# Sheet1.net
KiCad netlist of a schematic drawn in Altium Designer
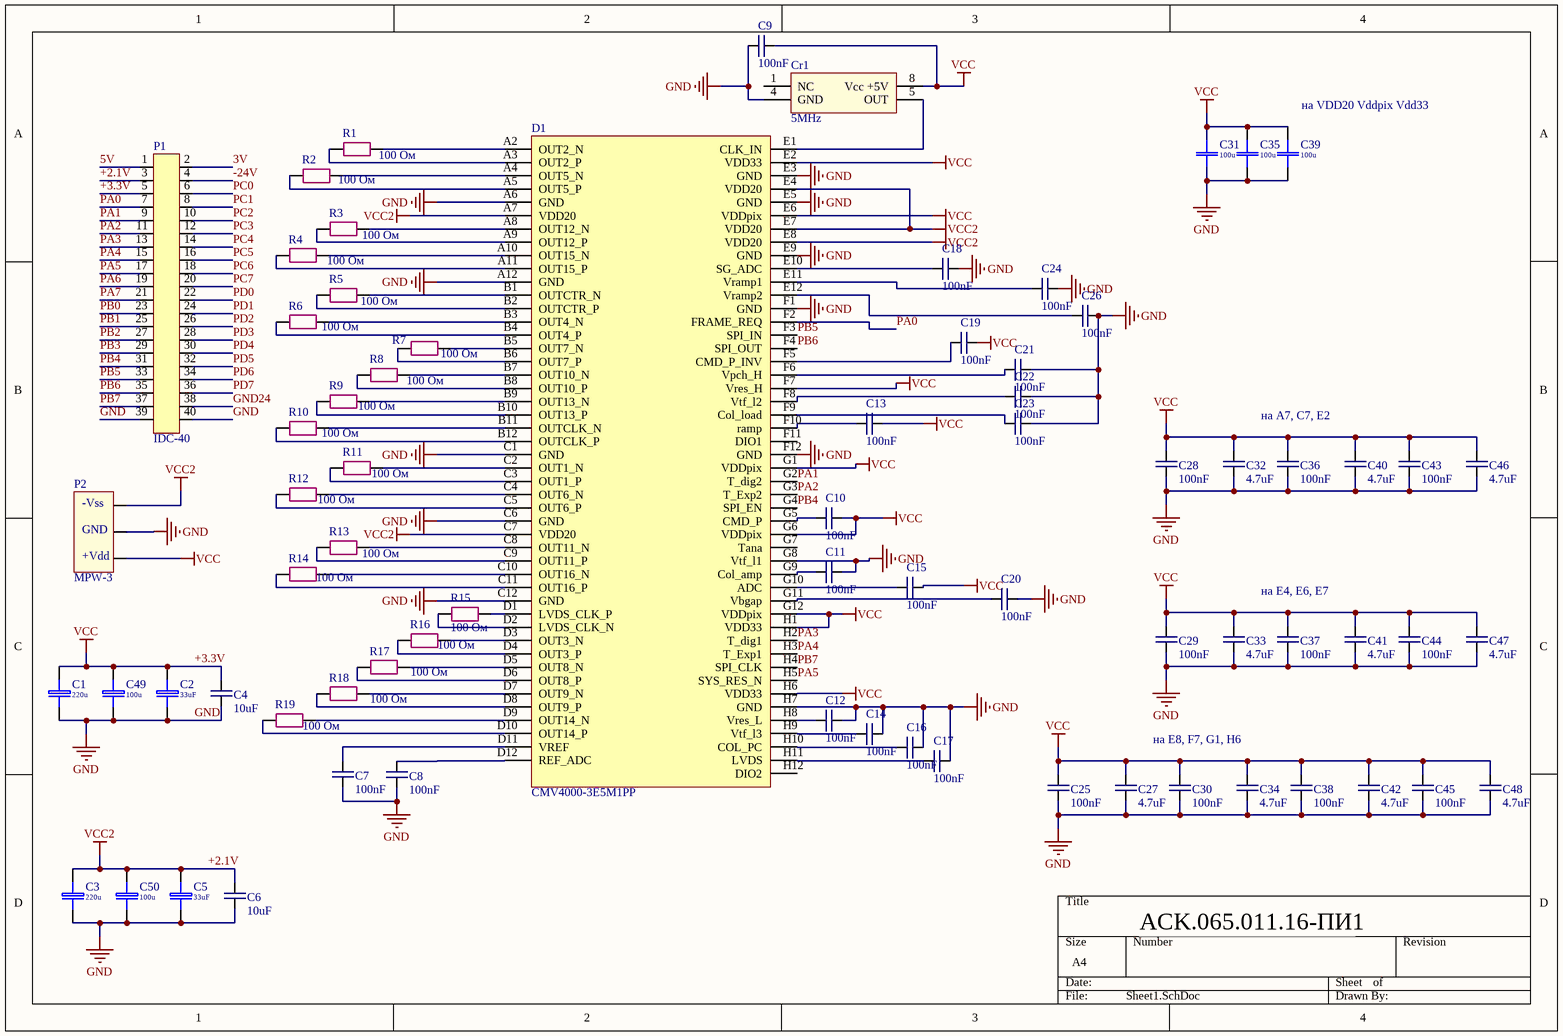
[diagram p0: Sheet1.SchDoc]

(export (version "E")
  (design (tool "Eeschema 10.0.6"))
  (components
    (comp (ref "C1")
      (value "220u")
      (footprint "EL SMD Case D D6.3x6.6 h7.7(0605)")
      (description "EL 25V SMD Case C D6.3x6.6 h7.7")
      (libsource (lib "SMD-RCL") (part "EL 100u/25V"))
    )
    (comp (ref "C2")
      (value "33uF")
      (footprint "EL Case B (3528-21)")
      (description "EL Tantalum Case B (3528-21)")
      (libsource (lib "SMD-RCL") (part "EL Case B (3528-21)"))
    )
    (comp (ref "C3")
      (value "220u")
      (footprint "EL SMD Case D D6.3x6.6 h7.7(0605)")
      (description "EL 25V SMD Case C D6.3x6.6 h7.7")
      (libsource (lib "SMD-RCL") (part "EL 100u/25V"))
    )
    (comp (ref "C4") (value "10uF") (footprint "RCU:C_0805") (libsource (lib "RCU") (part "capacitor 0805")))
    (comp (ref "C5")
      (value "33uF")
      (footprint "EL Case B (3528-21)")
      (description "EL Tantalum Case B (3528-21)")
      (libsource (lib "SMD-RCL") (part "EL Case B (3528-21)"))
    )
    (comp (ref "C6") (value "10uF") (footprint "RCU:C_0805") (libsource (lib "RCU") (part "capacitor 0805")))
    (comp (ref "C7") (value "100nF") (footprint "RCU:C_0805") (libsource (lib "RCU") (part "capacitor 0805")))
    (comp (ref "C8") (value "100nF") (footprint "RCU:C_0805") (libsource (lib "RCU") (part "capacitor 0805")))
    (comp (ref "C9") (value "100nF") (footprint "RCU:C_0805") (libsource (lib "RCU") (part "capacitor 0805")))
    (comp (ref "C10")
      (value "100nF")
      (footprint "RCU:C_0805")
      (libsource (lib "RCU") (part "capacitor 0805"))
    )
    (comp (ref "C11")
      (value "100nF")
      (footprint "RCU:C_0805")
      (libsource (lib "RCU") (part "capacitor 0805"))
    )
    (comp (ref "C12")
      (value "100nF")
      (footprint "RCU:C_0805")
      (libsource (lib "RCU") (part "capacitor 0805"))
    )
    (comp (ref "C13")
      (value "100nF")
      (footprint "RCU:C_0805")
      (libsource (lib "RCU") (part "capacitor 0805"))
    )
    (comp (ref "C14")
      (value "100nF")
      (footprint "RCU:C_0805")
      (libsource (lib "RCU") (part "capacitor 0805"))
    )
    (comp (ref "C15")
      (value "100nF")
      (footprint "RCU:C_0805")
      (libsource (lib "RCU") (part "capacitor 0805"))
    )
    (comp (ref "C16")
      (value "100nF")
      (footprint "RCU:C_0805")
      (libsource (lib "RCU") (part "capacitor 0805"))
    )
    (comp (ref "C17")
      (value "100nF")
      (footprint "RCU:C_0805")
      (libsource (lib "RCU") (part "capacitor 0805"))
    )
    (comp (ref "C18")
      (value "100nF")
      (footprint "RCU:C_0805")
      (libsource (lib "RCU") (part "capacitor 0805"))
    )
    (comp (ref "C19")
      (value "100nF")
      (footprint "RCU:C_0805")
      (libsource (lib "RCU") (part "capacitor 0805"))
    )
    (comp (ref "C20")
      (value "100nF")
      (footprint "RCU:C_0805")
      (libsource (lib "RCU") (part "capacitor 0805"))
    )
    (comp (ref "C21")
      (value "100nF")
      (footprint "RCU:C_0805")
      (libsource (lib "RCU") (part "capacitor 0805"))
    )
    (comp (ref "C22")
      (value "100nF")
      (footprint "RCU:C_0805")
      (libsource (lib "RCU") (part "capacitor 0805"))
    )
    (comp (ref "C23")
      (value "100nF")
      (footprint "RCU:C_0805")
      (libsource (lib "RCU") (part "capacitor 0805"))
    )
    (comp (ref "C24")
      (value "100nF")
      (footprint "RCU:C_0805")
      (libsource (lib "RCU") (part "capacitor 0805"))
    )
    (comp (ref "C25")
      (value "100nF")
      (footprint "RCU:C_0805")
      (libsource (lib "RCU") (part "capacitor 0805"))
    )
    (comp (ref "C26")
      (value "100nF")
      (footprint "RCU:C_0805")
      (libsource (lib "RCU") (part "capacitor 0805"))
    )
    (comp (ref "C27")
      (value "4.7uF")
      (footprint "RCU:C_0805")
      (libsource (lib "RCU") (part "capacitor 0805"))
    )
    (comp (ref "C28")
      (value "100nF")
      (footprint "RCU:C_0805")
      (libsource (lib "RCU") (part "capacitor 0805"))
    )
    (comp (ref "C29")
      (value "100nF")
      (footprint "RCU:C_0805")
      (libsource (lib "RCU") (part "capacitor 0805"))
    )
    (comp (ref "C30")
      (value "100nF")
      (footprint "RCU:C_0805")
      (libsource (lib "RCU") (part "capacitor 0805"))
    )
    (comp (ref "C31")
      (value "100u")
      (footprint "C1206(3216)")
      (description "SMD-1206 1000V X7R 10%")
      (libsource (lib "SMD-RCL") (part "C-1206  1000V 1n"))
    )
    (comp (ref "C32")
      (value "4.7uF")
      (footprint "RCU:C_0805")
      (libsource (lib "RCU") (part "capacitor 0805"))
    )
    (comp (ref "C33")
      (value "4.7uF")
      (footprint "RCU:C_0805")
      (libsource (lib "RCU") (part "capacitor 0805"))
    )
    (comp (ref "C34")
      (value "4.7uF")
      (footprint "RCU:C_0805")
      (libsource (lib "RCU") (part "capacitor 0805"))
    )
    (comp (ref "C35")
      (value "100u")
      (footprint "C1206(3216)")
      (description "SMD-1206 1000V X7R 10%")
      (libsource (lib "SMD-RCL") (part "C-1206  1000V 1n"))
    )
    (comp (ref "C36")
      (value "100nF")
      (footprint "RCU:C_0805")
      (libsource (lib "RCU") (part "capacitor 0805"))
    )
    (comp (ref "C37")
      (value "100nF")
      (footprint "RCU:C_0805")
      (libsource (lib "RCU") (part "capacitor 0805"))
    )
    (comp (ref "C38")
      (value "100nF")
      (footprint "RCU:C_0805")
      (libsource (lib "RCU") (part "capacitor 0805"))
    )
    (comp (ref "C39")
      (value "100u")
      (footprint "C1206(3216)")
      (description "SMD-1206 1000V X7R 10%")
      (libsource (lib "SMD-RCL") (part "C-1206  1000V 1n"))
    )
    (comp (ref "C40")
      (value "4.7uF")
      (footprint "RCU:C_0805")
      (libsource (lib "RCU") (part "capacitor 0805"))
    )
    (comp (ref "C41")
      (value "4.7uF")
      (footprint "RCU:C_0805")
      (libsource (lib "RCU") (part "capacitor 0805"))
    )
    (comp (ref "C42")
      (value "4.7uF")
      (footprint "RCU:C_0805")
      (libsource (lib "RCU") (part "capacitor 0805"))
    )
    (comp (ref "C43")
      (value "100nF")
      (footprint "RCU:C_0805")
      (libsource (lib "RCU") (part "capacitor 0805"))
    )
    (comp (ref "C44")
      (value "100nF")
      (footprint "RCU:C_0805")
      (libsource (lib "RCU") (part "capacitor 0805"))
    )
    (comp (ref "C45")
      (value "100nF")
      (footprint "RCU:C_0805")
      (libsource (lib "RCU") (part "capacitor 0805"))
    )
    (comp (ref "C46")
      (value "4.7uF")
      (footprint "RCU:C_0805")
      (libsource (lib "RCU") (part "capacitor 0805"))
    )
    (comp (ref "C47")
      (value "4.7uF")
      (footprint "RCU:C_0805")
      (libsource (lib "RCU") (part "capacitor 0805"))
    )
    (comp (ref "C48")
      (value "4.7uF")
      (footprint "RCU:C_0805")
      (libsource (lib "RCU") (part "capacitor 0805"))
    )
    (comp (ref "C49")
      (value "100u")
      (footprint "EL SMD Case D D6.3x6.6 h7.7(0605)")
      (description "EL 25V SMD Case C D6.3x6.6 h7.7")
      (libsource (lib "SMD-RCL") (part "EL 100u/25V"))
    )
    (comp (ref "C50")
      (value "100u")
      (footprint "EL SMD Case D D6.3x6.6 h7.7(0605)")
      (description "EL 25V SMD Case C D6.3x6.6 h7.7")
      (libsource (lib "SMD-RCL") (part "EL 100u/25V"))
    )
    (comp (ref "Cr1")
      (value "5MHz")
      (footprint "quarts_gen_2.54")
      (libsource (lib "RCU") (part "quarts_gen_2.54"))
    )
    (comp (ref "D1")
      (value "CMV4000-3E5M1PP")
      (footprint "cmv4000")
      (libsource (lib "RCU") (part "CMV4000-3E5M1PP"))
    )
    (comp (ref "P1")
      (value "IDC-40")
      (footprint "IDC-40")
      (description "разъем 2529")
      (libsource (lib "RCU") (part "IDC-40"))
    )
    (comp (ref "P2") (value "MPW-3") (footprint "MPW-3") (libsource (lib "RCU") (part "MPW-3")))
    (comp (ref "R1") (value "100 Ом") (footprint "RCU:R_0805") (libsource (lib "RCU") (part "resistor 0805")))
    (comp (ref "R2") (value "100 Ом") (footprint "RCU:R_0805") (libsource (lib "RCU") (part "100 Ом")))
    (comp (ref "R3") (value "100 Ом") (footprint "RCU:R_0805") (libsource (lib "RCU") (part "100 Ом")))
    (comp (ref "R4") (value "100 Ом") (footprint "RCU:R_0805") (libsource (lib "RCU") (part "100 Ом")))
    (comp (ref "R5") (value "100 Ом") (footprint "RCU:R_0805") (libsource (lib "RCU") (part "100 Ом")))
    (comp (ref "R6") (value "100 Ом") (footprint "RCU:R_0805") (libsource (lib "RCU") (part "100 Ом")))
    (comp (ref "R7") (value "100 Ом") (footprint "RCU:R_0805") (libsource (lib "RCU") (part "100 Ом")))
    (comp (ref "R8") (value "100 Ом") (footprint "RCU:R_0805") (libsource (lib "RCU") (part "100 Ом")))
    (comp (ref "R9") (value "100 Ом") (footprint "RCU:R_0805") (libsource (lib "RCU") (part "100 Ом")))
    (comp (ref "R10") (value "100 Ом") (footprint "RCU:R_0805") (libsource (lib "RCU") (part "100 Ом")))
    (comp (ref "R11") (value "100 Ом") (footprint "RCU:R_0805") (libsource (lib "RCU") (part "100 Ом")))
    (comp (ref "R12") (value "100 Ом") (footprint "RCU:R_0805") (libsource (lib "RCU") (part "100 Ом")))
    (comp (ref "R13") (value "100 Ом") (footprint "RCU:R_0805") (libsource (lib "RCU") (part "100 Ом")))
    (comp (ref "R14") (value "100 Ом") (footprint "RCU:R_0805") (libsource (lib "RCU") (part "100 Ом")))
    (comp (ref "R15") (value "100 Ом") (footprint "RCU:R_0805") (libsource (lib "RCU") (part "100 Ом")))
    (comp (ref "R16") (value "100 Ом") (footprint "RCU:R_0805") (libsource (lib "RCU") (part "100 Ом")))
    (comp (ref "R17") (value "100 Ом") (footprint "RCU:R_0805") (libsource (lib "RCU") (part "100 Ом")))
    (comp (ref "R18") (value "100 Ом") (footprint "RCU:R_0805") (libsource (lib "RCU") (part "100 Ом")))
    (comp (ref "R19") (value "100 Ом") (footprint "RCU:R_0805") (libsource (lib "RCU") (part "100 Ом")))
  )
  (nets
    (net (code "1") (name "/-24V") (class "Default")
      (node (ref "P1") (pin "4") (pinfunction "4_4") (pintype "passive"))
    )
    (net (code "2") (name "/3V") (class "Default")
      (node (ref "P1") (pin "2") (pinfunction "2_2") (pintype "passive"))
    )
    (net (code "3") (name "/5V") (class "Default")
      (node (ref "P1") (pin "1") (pinfunction "0_1") (pintype "passive"))
    )
    (net (code "4") (name "/GND24") (class "Default")
      (node (ref "P1") (pin "38") (pinfunction "38_38") (pintype "passive"))
    )
    (net (code "5") (name "/PA0") (class "Default")
      (node (ref "D1") (pin "F2") (pinfunction "FRAME_REQ_F2") (pintype "passive"))
      (node (ref "P1") (pin "7") (pinfunction "7_7") (pintype "passive"))
    )
    (net (code "6") (name "/PA1") (class "Default")
      (node (ref "D1") (pin "G2") (pinfunction "T_dig2_G2") (pintype "passive"))
      (node (ref "P1") (pin "9") (pinfunction "9_9") (pintype "passive"))
    )
    (net (code "7") (name "/PA2") (class "Default")
      (node (ref "D1") (pin "G3") (pinfunction "T_Exp2_G3") (pintype "passive"))
      (node (ref "P1") (pin "11") (pinfunction "11_11") (pintype "passive"))
    )
    (net (code "8") (name "/PA3") (class "Default")
      (node (ref "D1") (pin "H2") (pinfunction "T_dig1_H2") (pintype "passive"))
      (node (ref "P1") (pin "13") (pinfunction "13_13") (pintype "passive"))
    )
    (net (code "9") (name "/PA4") (class "Default")
      (node (ref "D1") (pin "H3") (pinfunction "T_Exp1_H3") (pintype "passive"))
      (node (ref "P1") (pin "15") (pinfunction "15_15") (pintype "passive"))
    )
    (net (code "10") (name "/PA5") (class "Default")
      (node (ref "D1") (pin "H5") (pinfunction "SYS_RES_N_H5") (pintype "passive"))
      (node (ref "P1") (pin "17") (pinfunction "17_17") (pintype "passive"))
    )
    (net (code "11") (name "/PA6") (class "Default")
      (node (ref "P1") (pin "19") (pinfunction "19_19") (pintype "passive"))
    )
    (net (code "12") (name "/PA7") (class "Default")
      (node (ref "P1") (pin "21") (pinfunction "21_21") (pintype "passive"))
    )
    (net (code "13") (name "/PB0") (class "Default")
      (node (ref "P1") (pin "23") (pinfunction "23_23") (pintype "passive"))
    )
    (net (code "14") (name "/PB1") (class "Default")
      (node (ref "P1") (pin "25") (pinfunction "25_25") (pintype "passive"))
    )
    (net (code "15") (name "/PB2") (class "Default")
      (node (ref "P1") (pin "27") (pinfunction "27_27") (pintype "passive"))
    )
    (net (code "16") (name "/PB3") (class "Default")
      (node (ref "P1") (pin "29") (pinfunction "29_29") (pintype "passive"))
    )
    (net (code "17") (name "/PB4") (class "Default")
      (node (ref "D1") (pin "G4") (pinfunction "SPI_EN_G4") (pintype "passive"))
      (node (ref "P1") (pin "31") (pinfunction "31_31") (pintype "passive"))
    )
    (net (code "18") (name "/PB5") (class "Default")
      (node (ref "D1") (pin "F3") (pinfunction "SPI_IN_F3") (pintype "passive"))
      (node (ref "P1") (pin "33") (pinfunction "33_33") (pintype "passive"))
    )
    (net (code "19") (name "/PB6") (class "Default")
      (node (ref "D1") (pin "F4") (pinfunction "SPI_OUT_F4") (pintype "passive"))
      (node (ref "P1") (pin "35") (pinfunction "35_35") (pintype "passive"))
    )
    (net (code "20") (name "/PB7") (class "Default")
      (node (ref "D1") (pin "H4") (pinfunction "SPI_CLK_H4") (pintype "passive"))
      (node (ref "P1") (pin "37") (pinfunction "37_37") (pintype "passive"))
    )
    (net (code "21") (name "/PC0") (class "Default")
      (node (ref "P1") (pin "6") (pinfunction "6_6") (pintype "passive"))
    )
    (net (code "22") (name "/PC1") (class "Default")
      (node (ref "P1") (pin "8") (pinfunction "8_8") (pintype "passive"))
    )
    (net (code "23") (name "/PC2") (class "Default")
      (node (ref "P1") (pin "10") (pinfunction "10_10") (pintype "passive"))
    )
    (net (code "24") (name "/PC3") (class "Default")
      (node (ref "P1") (pin "12") (pinfunction "12_12") (pintype "passive"))
    )
    (net (code "25") (name "/PC4") (class "Default")
      (node (ref "P1") (pin "14") (pinfunction "14_14") (pintype "passive"))
    )
    (net (code "26") (name "/PC5") (class "Default")
      (node (ref "P1") (pin "16") (pinfunction "16_16") (pintype "passive"))
    )
    (net (code "27") (name "/PC6") (class "Default")
      (node (ref "P1") (pin "18") (pinfunction "18_18") (pintype "passive"))
    )
    (net (code "28") (name "/PC7") (class "Default")
      (node (ref "P1") (pin "20") (pinfunction "20_20") (pintype "passive"))
    )
    (net (code "29") (name "/PD0") (class "Default")
      (node (ref "P1") (pin "22") (pinfunction "22_22") (pintype "passive"))
    )
    (net (code "30") (name "/PD1") (class "Default")
      (node (ref "P1") (pin "24") (pinfunction "24_24") (pintype "passive"))
    )
    (net (code "31") (name "/PD2") (class "Default")
      (node (ref "P1") (pin "26") (pinfunction "26_26") (pintype "passive"))
    )
    (net (code "32") (name "/PD3") (class "Default")
      (node (ref "P1") (pin "28") (pinfunction "28_28") (pintype "passive"))
    )
    (net (code "33") (name "/PD4") (class "Default")
      (node (ref "P1") (pin "30") (pinfunction "30_30") (pintype "passive"))
    )
    (net (code "34") (name "/PD5") (class "Default")
      (node (ref "P1") (pin "32") (pinfunction "32_32") (pintype "passive"))
    )
    (net (code "35") (name "/PD6") (class "Default")
      (node (ref "P1") (pin "34") (pinfunction "34_34") (pintype "passive"))
    )
    (net (code "36") (name "/PD7") (class "Default")
      (node (ref "P1") (pin "36") (pinfunction "36_36") (pintype "passive"))
    )
    (net (code "37") (name "GND") (class "Default")
      (node (ref "C1") (pin "2") (pinfunction "-_2") (pintype "passive"))
      (node (ref "C11") (pin "1") (pinfunction "1_1") (pintype "passive"))
      (node (ref "C12") (pin "1") (pinfunction "1_1") (pintype "passive"))
      (node (ref "C14") (pin "1") (pinfunction "1_1") (pintype "passive"))
      (node (ref "C16") (pin "1") (pinfunction "1_1") (pintype "passive"))
      (node (ref "C17") (pin "1") (pinfunction "1_1") (pintype "passive"))
      (node (ref "C18") (pin "1") (pinfunction "1_1") (pintype "passive"))
      (node (ref "C2") (pin "2") (pinfunction "-_2") (pintype "passive"))
      (node (ref "C20") (pin "1") (pinfunction "1_1") (pintype "passive"))
      (node (ref "C21") (pin "1") (pinfunction "1_1") (pintype "passive"))
      (node (ref "C22") (pin "1") (pinfunction "1_1") (pintype "passive"))
      (node (ref "C23") (pin "1") (pinfunction "1_1") (pintype "passive"))
      (node (ref "C24") (pin "1") (pinfunction "1_1") (pintype "passive"))
      (node (ref "C25") (pin "2") (pinfunction "2_2") (pintype "passive"))
      (node (ref "C26") (pin "1") (pinfunction "1_1") (pintype "passive"))
      (node (ref "C27") (pin "2") (pinfunction "2_2") (pintype "passive"))
      (node (ref "C28") (pin "2") (pinfunction "2_2") (pintype "passive"))
      (node (ref "C29") (pin "2") (pinfunction "2_2") (pintype "passive"))
      (node (ref "C3") (pin "2") (pinfunction "-_2") (pintype "passive"))
      (node (ref "C30") (pin "2") (pinfunction "2_2") (pintype "passive"))
      (node (ref "C31") (pin "2") (pinfunction "2_2") (pintype "passive"))
      (node (ref "C32") (pin "2") (pinfunction "2_2") (pintype "passive"))
      (node (ref "C33") (pin "2") (pinfunction "2_2") (pintype "passive"))
      (node (ref "C34") (pin "2") (pinfunction "2_2") (pintype "passive"))
      (node (ref "C35") (pin "2") (pinfunction "2_2") (pintype "passive"))
      (node (ref "C36") (pin "2") (pinfunction "2_2") (pintype "passive"))
      (node (ref "C37") (pin "2") (pinfunction "2_2") (pintype "passive"))
      (node (ref "C38") (pin "2") (pinfunction "2_2") (pintype "passive"))
      (node (ref "C39") (pin "2") (pinfunction "2_2") (pintype "passive"))
      (node (ref "C4") (pin "1") (pinfunction "1_1") (pintype "passive"))
      (node (ref "C40") (pin "2") (pinfunction "2_2") (pintype "passive"))
      (node (ref "C41") (pin "2") (pinfunction "2_2") (pintype "passive"))
      (node (ref "C42") (pin "2") (pinfunction "2_2") (pintype "passive"))
      (node (ref "C43") (pin "2") (pinfunction "2_2") (pintype "passive"))
      (node (ref "C44") (pin "2") (pinfunction "2_2") (pintype "passive"))
      (node (ref "C45") (pin "2") (pinfunction "2_2") (pintype "passive"))
      (node (ref "C46") (pin "2") (pinfunction "2_2") (pintype "passive"))
      (node (ref "C47") (pin "2") (pinfunction "2_2") (pintype "passive"))
      (node (ref "C48") (pin "2") (pinfunction "2_2") (pintype "passive"))
      (node (ref "C49") (pin "2") (pinfunction "-_2") (pintype "passive"))
      (node (ref "C5") (pin "2") (pinfunction "-_2") (pintype "passive"))
      (node (ref "C50") (pin "2") (pinfunction "-_2") (pintype "passive"))
      (node (ref "C6") (pin "1") (pinfunction "1_1") (pintype "passive"))
      (node (ref "C7") (pin "1") (pinfunction "1_1") (pintype "passive"))
      (node (ref "C8") (pin "2") (pinfunction "2_2") (pintype "passive"))
      (node (ref "C9") (pin "2") (pinfunction "2_2") (pintype "passive"))
      (node (ref "Cr1") (pin "4") (pinfunction "GND_4") (pintype "passive"))
      (node (ref "D1") (pin "A12") (pinfunction "GND_A12") (pintype "passive"))
      (node (ref "D1") (pin "A6") (pinfunction "GND_A6") (pintype "passive"))
      (node (ref "D1") (pin "C1") (pinfunction "GND_C1") (pintype "passive"))
      (node (ref "D1") (pin "C12") (pinfunction "GND_C12") (pintype "passive"))
      (node (ref "D1") (pin "C6") (pinfunction "GND_C6") (pintype "passive"))
      (node (ref "D1") (pin "E3") (pinfunction "GND_E3") (pintype "passive"))
      (node (ref "D1") (pin "E5") (pinfunction "GND_E5") (pintype "passive"))
      (node (ref "D1") (pin "E9") (pinfunction "GND_E9") (pintype "passive"))
      (node (ref "D1") (pin "F1") (pinfunction "GND_F1") (pintype "passive"))
      (node (ref "D1") (pin "F12") (pinfunction "GND_F12") (pintype "passive"))
      (node (ref "D1") (pin "G8") (pinfunction "Vtf_l1_G8") (pintype "passive"))
      (node (ref "D1") (pin "H7") (pinfunction "GND_H7") (pintype "passive"))
      (node (ref "P1") (pin "39") (pinfunction "39_39") (pintype "passive"))
      (node (ref "P1") (pin "40") (pinfunction "40_40") (pintype "passive"))
      (node (ref "P2") (pin "2") (pinfunction "2_2") (pintype "passive"))
    )
    (net (code "38") (name "Net-(Cr1-OUT)") (class "Default")
      (node (ref "Cr1") (pin "5") (pinfunction "OUT_5") (pintype "passive"))
      (node (ref "D1") (pin "E1") (pinfunction "CLK_IN_E1") (pintype "passive"))
    )
    (net (code "39") (name "Net-(D1-ADC)") (class "Default")
      (node (ref "C15") (pin "2") (pinfunction "2_2") (pintype "passive"))
      (node (ref "D1") (pin "G10") (pinfunction "ADC_G10") (pintype "passive"))
    )
    (net (code "40") (name "Net-(D1-CMD_P)") (class "Default")
      (node (ref "C10") (pin "2") (pinfunction "2_2") (pintype "passive"))
      (node (ref "D1") (pin "G5") (pinfunction "CMD_P_G5") (pintype "passive"))
    )
    (net (code "41") (name "Net-(D1-CMD_P_INV)") (class "Default")
      (node (ref "C19") (pin "2") (pinfunction "2_2") (pintype "passive"))
      (node (ref "D1") (pin "F5") (pinfunction "CMD_P_INV_F5") (pintype "passive"))
    )
    (net (code "42") (name "Net-(D1-COL_PC)") (class "Default")
      (node (ref "C16") (pin "2") (pinfunction "2_2") (pintype "passive"))
      (node (ref "D1") (pin "H10") (pinfunction "COL_PC_H10") (pintype "passive"))
    )
    (net (code "43") (name "Net-(D1-Col_amp)") (class "Default")
      (node (ref "C11") (pin "2") (pinfunction "2_2") (pintype "passive"))
      (node (ref "D1") (pin "G9") (pinfunction "Col_amp_G9") (pintype "passive"))
    )
    (net (code "44") (name "Net-(D1-Col_load)") (class "Default")
      (node (ref "C23") (pin "2") (pinfunction "2_2") (pintype "passive"))
      (node (ref "D1") (pin "F9") (pinfunction "Col_load_F9") (pintype "passive"))
    )
    (net (code "45") (name "Net-(D1-LVDS)") (class "Default")
      (node (ref "C17") (pin "2") (pinfunction "2_2") (pintype "passive"))
      (node (ref "D1") (pin "H11") (pinfunction "LVDS_H11") (pintype "passive"))
    )
    (net (code "46") (name "Net-(D1-LVDS_CLK_N)") (class "Default")
      (node (ref "D1") (pin "D2") (pinfunction "LVDS_CLK_N_D2") (pintype "passive"))
      (node (ref "R15") (pin "1") (pinfunction "1_1") (pintype "passive"))
    )
    (net (code "47") (name "Net-(D1-LVDS_CLK_P)") (class "Default")
      (node (ref "D1") (pin "D1") (pinfunction "LVDS_CLK_P_D1") (pintype "passive"))
      (node (ref "R15") (pin "2") (pinfunction "2_2") (pintype "passive"))
    )
    (net (code "48") (name "Net-(D1-OUT1_N)") (class "Default")
      (node (ref "D1") (pin "C2") (pinfunction "OUT1_N_C2") (pintype "passive"))
      (node (ref "R11") (pin "2") (pinfunction "2_2") (pintype "passive"))
    )
    (net (code "49") (name "Net-(D1-OUT1_P)") (class "Default")
      (node (ref "D1") (pin "C3") (pinfunction "OUT1_P_C3") (pintype "passive"))
      (node (ref "R11") (pin "1") (pinfunction "1_1") (pintype "passive"))
    )
    (net (code "50") (name "Net-(D1-OUT2_N)") (class "Default")
      (node (ref "D1") (pin "A2") (pinfunction "OUT2_N_A2") (pintype "passive"))
      (node (ref "R1") (pin "2") (pinfunction "2_2") (pintype "passive"))
    )
    (net (code "51") (name "Net-(D1-OUT2_P)") (class "Default")
      (node (ref "D1") (pin "A3") (pinfunction "OUT2_P_A3") (pintype "passive"))
      (node (ref "R1") (pin "1") (pinfunction "1_1") (pintype "passive"))
    )
    (net (code "52") (name "Net-(D1-OUT3_N)") (class "Default")
      (node (ref "D1") (pin "D3") (pinfunction "OUT3_N_D3") (pintype "passive"))
      (node (ref "R16") (pin "2") (pinfunction "2_2") (pintype "passive"))
    )
    (net (code "53") (name "Net-(D1-OUT3_P)") (class "Default")
      (node (ref "D1") (pin "D4") (pinfunction "OUT3_P_D4") (pintype "passive"))
      (node (ref "R16") (pin "1") (pinfunction "1_1") (pintype "passive"))
    )
    (net (code "54") (name "Net-(D1-OUT4_N)") (class "Default")
      (node (ref "D1") (pin "B3") (pinfunction "OUT4_N_B3") (pintype "passive"))
      (node (ref "R6") (pin "2") (pinfunction "2_2") (pintype "passive"))
    )
    (net (code "55") (name "Net-(D1-OUT4_P)") (class "Default")
      (node (ref "D1") (pin "B4") (pinfunction "OUT4_P_B4") (pintype "passive"))
      (node (ref "R6") (pin "1") (pinfunction "1_1") (pintype "passive"))
    )
    (net (code "56") (name "Net-(D1-OUT5_N)") (class "Default")
      (node (ref "D1") (pin "A4") (pinfunction "OUT5_N_A4") (pintype "passive"))
      (node (ref "R2") (pin "2") (pinfunction "2_2") (pintype "passive"))
    )
    (net (code "57") (name "Net-(D1-OUT5_P)") (class "Default")
      (node (ref "D1") (pin "A5") (pinfunction "OUT5_P_A5") (pintype "passive"))
      (node (ref "R2") (pin "1") (pinfunction "1_1") (pintype "passive"))
    )
    (net (code "58") (name "Net-(D1-OUT6_N)") (class "Default")
      (node (ref "D1") (pin "C4") (pinfunction "OUT6_N_C4") (pintype "passive"))
      (node (ref "R12") (pin "2") (pinfunction "2_2") (pintype "passive"))
    )
    (net (code "59") (name "Net-(D1-OUT6_P)") (class "Default")
      (node (ref "D1") (pin "C5") (pinfunction "OUT6_P_C5") (pintype "passive"))
      (node (ref "R12") (pin "1") (pinfunction "1_1") (pintype "passive"))
    )
    (net (code "60") (name "Net-(D1-OUT7_N)") (class "Default")
      (node (ref "D1") (pin "B5") (pinfunction "OUT7_N_B5") (pintype "passive"))
      (node (ref "R7") (pin "2") (pinfunction "2_2") (pintype "passive"))
    )
    (net (code "61") (name "Net-(D1-OUT7_P)") (class "Default")
      (node (ref "D1") (pin "B6") (pinfunction "OUT7_P_B6") (pintype "passive"))
      (node (ref "R7") (pin "1") (pinfunction "1_1") (pintype "passive"))
    )
    (net (code "62") (name "Net-(D1-OUT8_N)") (class "Default")
      (node (ref "D1") (pin "D5") (pinfunction "OUT8_N_D5") (pintype "passive"))
      (node (ref "R17") (pin "2") (pinfunction "2_2") (pintype "passive"))
    )
    (net (code "63") (name "Net-(D1-OUT8_P)") (class "Default")
      (node (ref "D1") (pin "D6") (pinfunction "OUT8_P_D6") (pintype "passive"))
      (node (ref "R17") (pin "1") (pinfunction "1_1") (pintype "passive"))
    )
    (net (code "64") (name "Net-(D1-OUT9_N)") (class "Default")
      (node (ref "D1") (pin "D7") (pinfunction "OUT9_N_D7") (pintype "passive"))
      (node (ref "R18") (pin "2") (pinfunction "2_2") (pintype "passive"))
    )
    (net (code "65") (name "Net-(D1-OUT9_P)") (class "Default")
      (node (ref "D1") (pin "D8") (pinfunction "OUT9_P_D8") (pintype "passive"))
      (node (ref "R18") (pin "1") (pinfunction "1_1") (pintype "passive"))
    )
    (net (code "66") (name "Net-(D1-OUT10_N)") (class "Default")
      (node (ref "D1") (pin "B7") (pinfunction "OUT10_N_B7") (pintype "passive"))
      (node (ref "R8") (pin "2") (pinfunction "2_2") (pintype "passive"))
    )
    (net (code "67") (name "Net-(D1-OUT10_P)") (class "Default")
      (node (ref "D1") (pin "B8") (pinfunction "OUT10_P_B8") (pintype "passive"))
      (node (ref "R8") (pin "1") (pinfunction "1_1") (pintype "passive"))
    )
    (net (code "68") (name "Net-(D1-OUT11_N)") (class "Default")
      (node (ref "D1") (pin "C8") (pinfunction "OUT11_N_C8") (pintype "passive"))
      (node (ref "R13") (pin "2") (pinfunction "2_2") (pintype "passive"))
    )
    (net (code "69") (name "Net-(D1-OUT11_P)") (class "Default")
      (node (ref "D1") (pin "C9") (pinfunction "OUT11_P_C9") (pintype "passive"))
      (node (ref "R13") (pin "1") (pinfunction "1_1") (pintype "passive"))
    )
    (net (code "70") (name "Net-(D1-OUT12_N)") (class "Default")
      (node (ref "D1") (pin "A8") (pinfunction "OUT12_N_A8") (pintype "passive"))
      (node (ref "R3") (pin "2") (pinfunction "2_2") (pintype "passive"))
    )
    (net (code "71") (name "Net-(D1-OUT12_P)") (class "Default")
      (node (ref "D1") (pin "A9") (pinfunction "OUT12_P_A9") (pintype "passive"))
      (node (ref "R3") (pin "1") (pinfunction "1_1") (pintype "passive"))
    )
    (net (code "72") (name "Net-(D1-OUT13_N)") (class "Default")
      (node (ref "D1") (pin "B9") (pinfunction "OUT13_N_B9") (pintype "passive"))
      (node (ref "R9") (pin "2") (pinfunction "2_2") (pintype "passive"))
    )
    (net (code "73") (name "Net-(D1-OUT13_P)") (class "Default")
      (node (ref "D1") (pin "B10") (pinfunction "OUT13_P_B10") (pintype "passive"))
      (node (ref "R9") (pin "1") (pinfunction "1_1") (pintype "passive"))
    )
    (net (code "74") (name "Net-(D1-OUT14_N)") (class "Default")
      (node (ref "D1") (pin "D9") (pinfunction "OUT14_N_D9") (pintype "passive"))
      (node (ref "R19") (pin "2") (pinfunction "2_2") (pintype "passive"))
    )
    (net (code "75") (name "Net-(D1-OUT14_P)") (class "Default")
      (node (ref "D1") (pin "D10") (pinfunction "OUT14_P_D10") (pintype "passive"))
      (node (ref "R19") (pin "1") (pinfunction "1_1") (pintype "passive"))
    )
    (net (code "76") (name "Net-(D1-OUT15_N)") (class "Default")
      (node (ref "D1") (pin "A10") (pinfunction "OUT15_N_A10") (pintype "passive"))
      (node (ref "R4") (pin "2") (pinfunction "2_2") (pintype "passive"))
    )
    (net (code "77") (name "Net-(D1-OUT15_P)") (class "Default")
      (node (ref "D1") (pin "A11") (pinfunction "OUT15_P_A11") (pintype "passive"))
      (node (ref "R4") (pin "1") (pinfunction "1_1") (pintype "passive"))
    )
    (net (code "78") (name "Net-(D1-OUT16_N)") (class "Default")
      (node (ref "D1") (pin "C10") (pinfunction "OUT16_N_C10") (pintype "passive"))
      (node (ref "R14") (pin "2") (pinfunction "2_2") (pintype "passive"))
    )
    (net (code "79") (name "Net-(D1-OUT16_P)") (class "Default")
      (node (ref "D1") (pin "C11") (pinfunction "OUT16_P_C11") (pintype "passive"))
      (node (ref "R14") (pin "1") (pinfunction "1_1") (pintype "passive"))
    )
    (net (code "80") (name "Net-(D1-OUTCLK_N)") (class "Default")
      (node (ref "D1") (pin "B11") (pinfunction "OUTCLK_N_B11") (pintype "passive"))
      (node (ref "R10") (pin "2") (pinfunction "2_2") (pintype "passive"))
    )
    (net (code "81") (name "Net-(D1-OUTCLK_P)") (class "Default")
      (node (ref "D1") (pin "B12") (pinfunction "OUTCLK_P_B12") (pintype "passive"))
      (node (ref "R10") (pin "1") (pinfunction "1_1") (pintype "passive"))
    )
    (net (code "82") (name "Net-(D1-OUTCTR_N)") (class "Default")
      (node (ref "D1") (pin "B1") (pinfunction "OUTCTR_N_B1") (pintype "passive"))
      (node (ref "R5") (pin "2") (pinfunction "2_2") (pintype "passive"))
    )
    (net (code "83") (name "Net-(D1-OUTCTR_P)") (class "Default")
      (node (ref "D1") (pin "B2") (pinfunction "OUTCTR_P_B2") (pintype "passive"))
      (node (ref "R5") (pin "1") (pinfunction "1_1") (pintype "passive"))
    )
    (net (code "84") (name "Net-(D1-REF_ADC)") (class "Default")
      (node (ref "C8") (pin "1") (pinfunction "1_1") (pintype "passive"))
      (node (ref "D1") (pin "D12") (pinfunction "REF_ADC_D12") (pintype "passive"))
    )
    (net (code "85") (name "Net-(D1-SG_ADC)") (class "Default")
      (node (ref "C18") (pin "2") (pinfunction "2_2") (pintype "passive"))
      (node (ref "D1") (pin "E10") (pinfunction "SG_ADC_E10") (pintype "passive"))
    )
    (net (code "86") (name "Net-(D1-VREF)") (class "Default")
      (node (ref "C7") (pin "2") (pinfunction "2_2") (pintype "passive"))
      (node (ref "D1") (pin "D11") (pinfunction "VREF_D11") (pintype "passive"))
    )
    (net (code "87") (name "Net-(D1-Vbgap)") (class "Default")
      (node (ref "C20") (pin "2") (pinfunction "2_2") (pintype "passive"))
      (node (ref "D1") (pin "G11") (pinfunction "Vbgap_G11") (pintype "passive"))
    )
    (net (code "88") (name "Net-(D1-Vpch_H)") (class "Default")
      (node (ref "C21") (pin "2") (pinfunction "2_2") (pintype "passive"))
      (node (ref "D1") (pin "F6") (pinfunction "Vpch_H_F6") (pintype "passive"))
    )
    (net (code "89") (name "Net-(D1-Vramp1)") (class "Default")
      (node (ref "C24") (pin "2") (pinfunction "2_2") (pintype "passive"))
      (node (ref "D1") (pin "E11") (pinfunction "Vramp1_E11") (pintype "passive"))
    )
    (net (code "90") (name "Net-(D1-Vramp2)") (class "Default")
      (node (ref "C26") (pin "2") (pinfunction "2_2") (pintype "passive"))
      (node (ref "D1") (pin "E12") (pinfunction "Vramp2_E12") (pintype "passive"))
    )
    (net (code "91") (name "Net-(D1-Vres_L)") (class "Default")
      (node (ref "C12") (pin "2") (pinfunction "2_2") (pintype "passive"))
      (node (ref "D1") (pin "H8") (pinfunction "Vres_L_H8") (pintype "passive"))
    )
    (net (code "92") (name "Net-(D1-Vtf_l2)") (class "Default")
      (node (ref "C22") (pin "2") (pinfunction "2_2") (pintype "passive"))
      (node (ref "D1") (pin "F8") (pinfunction "Vtf_l2_F8") (pintype "passive"))
    )
    (net (code "93") (name "Net-(D1-Vtf_l3)") (class "Default")
      (node (ref "C14") (pin "2") (pinfunction "2_2") (pintype "passive"))
      (node (ref "D1") (pin "H9") (pinfunction "Vtf_l3_H9") (pintype "passive"))
    )
    (net (code "94") (name "Net-(D1-ramp)") (class "Default")
      (node (ref "C13") (pin "2") (pinfunction "2_2") (pintype "passive"))
      (node (ref "D1") (pin "F10") (pinfunction "ramp_F10") (pintype "passive"))
    )
    (net (code "95") (name "VCC") (class "Default")
      (node (ref "C1") (pin "1") (pinfunction "+_1") (pintype "passive"))
      (node (ref "C10") (pin "1") (pinfunction "1_1") (pintype "passive"))
      (node (ref "C13") (pin "1") (pinfunction "1_1") (pintype "passive"))
      (node (ref "C15") (pin "1") (pinfunction "1_1") (pintype "passive"))
      (node (ref "C19") (pin "1") (pinfunction "1_1") (pintype "passive"))
      (node (ref "C2") (pin "1") (pinfunction "+_1") (pintype "passive"))
      (node (ref "C25") (pin "1") (pinfunction "1_1") (pintype "passive"))
      (node (ref "C27") (pin "1") (pinfunction "1_1") (pintype "passive"))
      (node (ref "C28") (pin "1") (pinfunction "1_1") (pintype "passive"))
      (node (ref "C29") (pin "1") (pinfunction "1_1") (pintype "passive"))
      (node (ref "C30") (pin "1") (pinfunction "1_1") (pintype "passive"))
      (node (ref "C31") (pin "1") (pinfunction "1_1") (pintype "passive"))
      (node (ref "C32") (pin "1") (pinfunction "1_1") (pintype "passive"))
      (node (ref "C33") (pin "1") (pinfunction "1_1") (pintype "passive"))
      (node (ref "C34") (pin "1") (pinfunction "1_1") (pintype "passive"))
      (node (ref "C35") (pin "1") (pinfunction "1_1") (pintype "passive"))
      (node (ref "C36") (pin "1") (pinfunction "1_1") (pintype "passive"))
      (node (ref "C37") (pin "1") (pinfunction "1_1") (pintype "passive"))
      (node (ref "C38") (pin "1") (pinfunction "1_1") (pintype "passive"))
      (node (ref "C39") (pin "1") (pinfunction "1_1") (pintype "passive"))
      (node (ref "C4") (pin "2") (pinfunction "2_2") (pintype "passive"))
      (node (ref "C40") (pin "1") (pinfunction "1_1") (pintype "passive"))
      (node (ref "C41") (pin "1") (pinfunction "1_1") (pintype "passive"))
      (node (ref "C42") (pin "1") (pinfunction "1_1") (pintype "passive"))
      (node (ref "C43") (pin "1") (pinfunction "1_1") (pintype "passive"))
      (node (ref "C44") (pin "1") (pinfunction "1_1") (pintype "passive"))
      (node (ref "C45") (pin "1") (pinfunction "1_1") (pintype "passive"))
      (node (ref "C46") (pin "1") (pinfunction "1_1") (pintype "passive"))
      (node (ref "C47") (pin "1") (pinfunction "1_1") (pintype "passive"))
      (node (ref "C48") (pin "1") (pinfunction "1_1") (pintype "passive"))
      (node (ref "C49") (pin "1") (pinfunction "+_1") (pintype "passive"))
      (node (ref "C9") (pin "1") (pinfunction "1_1") (pintype "passive"))
      (node (ref "Cr1") (pin "8") (pinfunction "Vcc_+5V_8") (pintype "passive"))
      (node (ref "D1") (pin "E2") (pinfunction "VDD33_E2") (pintype "passive"))
      (node (ref "D1") (pin "E6") (pinfunction "VDDpix_E6") (pintype "passive"))
      (node (ref "D1") (pin "F7") (pinfunction "Vres_H_F7") (pintype "passive"))
      (node (ref "D1") (pin "G1") (pinfunction "VDDpix_G1") (pintype "passive"))
      (node (ref "D1") (pin "G12") (pinfunction "VDDpix_G12") (pintype "passive"))
      (node (ref "D1") (pin "G6") (pinfunction "VDDpix_G6") (pintype "passive"))
      (node (ref "D1") (pin "H1") (pinfunction "VDD33_H1") (pintype "passive"))
      (node (ref "D1") (pin "H6") (pinfunction "VDD33_H6") (pintype "passive"))
      (node (ref "P1") (pin "5") (pinfunction "5_5") (pintype "passive"))
      (node (ref "P2") (pin "3") (pinfunction "3_3") (pintype "passive"))
    )
    (net (code "96") (name "VCC2") (class "Default")
      (node (ref "C3") (pin "1") (pinfunction "+_1") (pintype "passive"))
      (node (ref "C5") (pin "1") (pinfunction "+_1") (pintype "passive"))
      (node (ref "C50") (pin "1") (pinfunction "+_1") (pintype "passive"))
      (node (ref "C6") (pin "2") (pinfunction "2_2") (pintype "passive"))
      (node (ref "D1") (pin "A7") (pinfunction "VDD20_A7") (pintype "passive"))
      (node (ref "D1") (pin "C7") (pinfunction "VDD20_C7") (pintype "passive"))
      (node (ref "D1") (pin "E4") (pinfunction "VDD20_E4") (pintype "passive"))
      (node (ref "D1") (pin "E7") (pinfunction "VDD20_E7") (pintype "passive"))
      (node (ref "D1") (pin "E8") (pinfunction "VDD20_E8") (pintype "passive"))
      (node (ref "P1") (pin "3") (pinfunction "3_3") (pintype "passive"))
      (node (ref "P2") (pin "1") (pinfunction "1_1") (pintype "passive"))
    )
    (net (code "97") (name "unconnected-(Cr1-NC-Pad1)") (class "Default")
      (node (ref "Cr1") (pin "1") (pinfunction "NC_1") (pintype "passive"))
    )
    (net (code "98") (name "unconnected-(D1-DIO1-PadF11)") (class "Default")
      (node (ref "D1") (pin "F11") (pinfunction "DIO1_F11") (pintype "passive"))
    )
    (net (code "99") (name "unconnected-(D1-DIO2-PadH12)") (class "Default")
      (node (ref "D1") (pin "H12") (pinfunction "DIO2_H12") (pintype "passive"))
    )
    (net (code "100") (name "unconnected-(D1-Tana-PadG7)") (class "Default")
      (node (ref "D1") (pin "G7") (pinfunction "Tana_G7") (pintype "passive"))
    )
  )
)
